# PS2_board.net
KiCad netlist of a schematic drawn in EAGLE
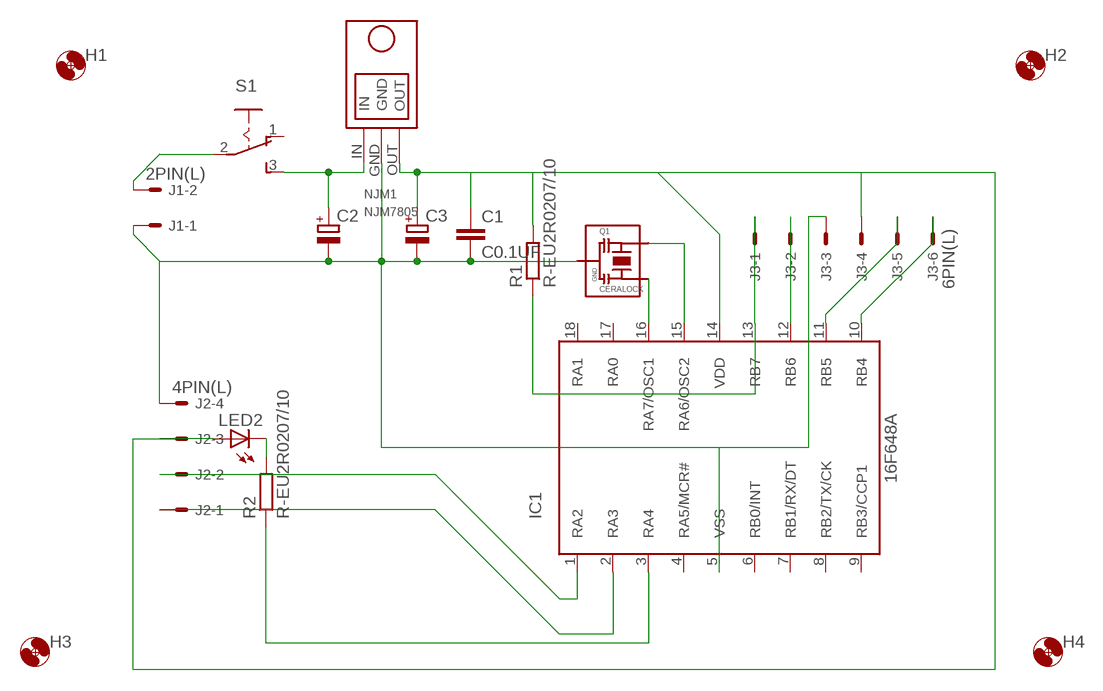
[diagram p0: schematic, sheet 1]

(export (version "E")
  (design (tool "Eeschema 10.0.6"))
  (components
    (comp (ref "C1")
      (value "C0.1UF")
      (footprint "eagle-import:C0.1UF")
      (libsource (lib "eagle-import") (part "C0.1UF"))
    )
    (comp (ref "C2")
      (value "CPOL-EU2-5MM")
      (footprint "eagle-import:E2-5")
      (libsource (lib "eagle-import") (part "CPOL-EU2-5MM"))
    )
    (comp (ref "C3")
      (value "CPOL-EU2-5MM")
      (footprint "eagle-import:E2-5")
      (libsource (lib "eagle-import") (part "CPOL-EU2-5MM"))
    )
    (comp (ref "H1")
      (value "HOLE3.3M3BOLT")
      (footprint "eagle-import:HOLE3.3")
      (libsource (lib "eagle-import") (part "HOLE3.3M3BOLT"))
    )
    (comp (ref "H2")
      (value "HOLE3.3M3BOLT")
      (footprint "eagle-import:HOLE3.3")
      (libsource (lib "eagle-import") (part "HOLE3.3M3BOLT"))
    )
    (comp (ref "H3")
      (value "HOLE3.3M3BOLT")
      (footprint "eagle-import:HOLE3.3")
      (libsource (lib "eagle-import") (part "HOLE3.3M3BOLT"))
    )
    (comp (ref "H4")
      (value "HOLE3.3M3BOLT")
      (footprint "eagle-import:HOLE3.3")
      (libsource (lib "eagle-import") (part "HOLE3.3M3BOLT"))
    )
    (comp (ref "IC1")
      (value "16F648A")
      (footprint "eagle-import:18PIN")
      (libsource (lib "eagle-import") (part "16F648A"))
    )
    (comp (ref "J1")
      (value "2PIN(L)")
      (footprint "eagle-import:2PL")
      (libsource (lib "eagle-import") (part "2PIN(L)"))
    )
    (comp (ref "J2")
      (value "4PIN(L)")
      (footprint "eagle-import:4PL")
      (libsource (lib "eagle-import") (part "4PIN(L)"))
    )
    (comp (ref "J3")
      (value "6PIN(L)")
      (footprint "eagle-import:6PL")
      (libsource (lib "eagle-import") (part "6PIN(L)"))
    )
    (comp (ref "LED2")
      (value "LED5MM")
      (footprint "eagle-import:LED5MM")
      (libsource (lib "eagle-import") (part "LED5MM"))
    )
    (comp (ref "NJM1")
      (value "NJM7805")
      (footprint "eagle-import:NJM7805")
      (libsource (lib "eagle-import") (part "NJM7805"))
    )
    (comp (ref "Q1")
      (value "CERALOCK")
      (footprint "eagle-import:CERALOCK")
      (libsource (lib "eagle-import") (part "CERALOCK"))
    )
    (comp (ref "R1")
      (value "R-EU2R0207/10")
      (footprint "eagle-import:0207_10")
      (libsource (lib "eagle-import") (part "R-EU2R0207/10"))
    )
    (comp (ref "R2")
      (value "R-EU2R0207/10")
      (footprint "eagle-import:0207_10")
      (libsource (lib "eagle-import") (part "R-EU2R0207/10"))
    )
    (comp (ref "S1")
      (value "SLIDESW")
      (footprint "eagle-import:SLIDESW")
      (libsource (lib "eagle-import") (part "SLIDESW"))
    )
  )
  (nets
    (net (code "1") (name "Net-(C2-Pad+)") (class "Default")
      (node (ref "C2") (pin "+") (pinfunction "+_+") (pintype "passive"))
      (node (ref "NJM1") (pin "IN") (pinfunction "IN_IN") (pintype "bidirectional"))
      (node (ref "S1") (pin "3") (pinfunction "3_3") (pintype "passive"))
    )
    (net (code "2") (name "Net-(IC1-RA2)") (class "Default")
      (node (ref "IC1") (pin "1") (pinfunction "RA2_1") (pintype "bidirectional"))
      (node (ref "J2") (pin "2") (pinfunction "S_2") (pintype "passive"))
    )
    (net (code "3") (name "Net-(IC1-RA3)") (class "Default")
      (node (ref "IC1") (pin "2") (pinfunction "RA3_2") (pintype "bidirectional"))
      (node (ref "J2") (pin "1") (pinfunction "S_1") (pintype "passive"))
    )
    (net (code "4") (name "Net-(IC1-RA4)") (class "Default")
      (node (ref "IC1") (pin "3") (pinfunction "RA4_3") (pintype "bidirectional"))
      (node (ref "R2") (pin "1") (pinfunction "1_1") (pintype "passive"))
    )
    (net (code "5") (name "Net-(IC1-RA6{slash}OSC2)") (class "Default")
      (node (ref "IC1") (pin "15") (pinfunction "RA6/OSC2_15") (pintype "bidirectional"))
      (node (ref "Q1") (pin "P$1") (pinfunction "P$1_P$1") (pintype "passive"))
    )
    (net (code "6") (name "Net-(IC1-RA7{slash}OSC1)") (class "Default")
      (node (ref "IC1") (pin "16") (pinfunction "RA7/OSC1_16") (pintype "bidirectional"))
      (node (ref "Q1") (pin "P$3") (pinfunction "P$3_P$3") (pintype "passive"))
    )
    (net (code "7") (name "Net-(IC1-RB4)") (class "Default")
      (node (ref "IC1") (pin "10") (pinfunction "RB4_10") (pintype "bidirectional"))
      (node (ref "J3") (pin "6") (pinfunction "S_6") (pintype "passive"))
    )
    (net (code "8") (name "Net-(IC1-RB5)") (class "Default")
      (node (ref "IC1") (pin "11") (pinfunction "RB5_11") (pintype "bidirectional"))
      (node (ref "J3") (pin "5") (pinfunction "S_5") (pintype "passive"))
    )
    (net (code "9") (name "Net-(IC1-RB6)") (class "Default")
      (node (ref "IC1") (pin "12") (pinfunction "RB6_12") (pintype "bidirectional"))
      (node (ref "J3") (pin "2") (pinfunction "S_2") (pintype "passive"))
    )
    (net (code "10") (name "Net-(IC1-RB7)") (class "Default")
      (node (ref "IC1") (pin "13") (pinfunction "RB7_13") (pintype "bidirectional"))
      (node (ref "J3") (pin "1") (pinfunction "S_1") (pintype "passive"))
      (node (ref "R1") (pin "1") (pinfunction "1_1") (pintype "passive"))
    )
    (net (code "11") (name "Net-(IC1-VDD)") (class "Default")
      (node (ref "C1") (pin "1") (pinfunction "1_1") (pintype "passive"))
      (node (ref "C3") (pin "+") (pinfunction "+_+") (pintype "passive"))
      (node (ref "IC1") (pin "14") (pinfunction "VDD_14") (pintype "power_in"))
      (node (ref "J2") (pin "3") (pinfunction "S_3") (pintype "passive"))
      (node (ref "J3") (pin "4") (pinfunction "S_4") (pintype "passive"))
      (node (ref "LED2") (pin "A") (pinfunction "A_A") (pintype "passive"))
      (node (ref "NJM1") (pin "OUT") (pinfunction "OUT_OUT") (pintype "bidirectional"))
      (node (ref "R1") (pin "2") (pinfunction "2_2") (pintype "passive"))
    )
    (net (code "12") (name "Net-(IC1-VSS)") (class "Default")
      (node (ref "C1") (pin "2") (pinfunction "2_2") (pintype "passive"))
      (node (ref "C2") (pin "-") (pinfunction "-_-") (pintype "passive"))
      (node (ref "C3") (pin "-") (pinfunction "-_-") (pintype "passive"))
      (node (ref "IC1") (pin "5") (pinfunction "VSS_5") (pintype "power_in"))
      (node (ref "J1") (pin "1") (pinfunction "S_1") (pintype "passive"))
      (node (ref "J2") (pin "4") (pinfunction "S_4") (pintype "passive"))
      (node (ref "J3") (pin "3") (pinfunction "S_3") (pintype "passive"))
      (node (ref "NJM1") (pin "GND") (pinfunction "GND_GND") (pintype "bidirectional"))
      (node (ref "Q1") (pin "P$2") (pinfunction "P$2_P$2") (pintype "passive"))
    )
    (net (code "13") (name "Net-(J1B-S)") (class "Default")
      (node (ref "J1") (pin "2") (pinfunction "S_2") (pintype "passive"))
      (node (ref "S1") (pin "2") (pinfunction "2_2") (pintype "passive"))
    )
    (net (code "14") (name "Net-(LED2-C)") (class "Default")
      (node (ref "LED2") (pin "K") (pinfunction "C_K") (pintype "passive"))
      (node (ref "R2") (pin "2") (pinfunction "2_2") (pintype "passive"))
    )
    (net (code "15") (name "unconnected-(IC1-RA0-Pad17)") (class "Default")
      (node (ref "IC1") (pin "17") (pinfunction "RA0_17") (pintype "bidirectional"))
    )
    (net (code "16") (name "unconnected-(IC1-RA1-Pad18)") (class "Default")
      (node (ref "IC1") (pin "18") (pinfunction "RA1_18") (pintype "bidirectional"))
    )
    (net (code "17") (name "unconnected-(IC1-RA5{slash}MCR#-Pad4)") (class "Default")
      (node (ref "IC1") (pin "4") (pinfunction "RA5/MCR#_4") (pintype "input"))
    )
    (net (code "18") (name "unconnected-(IC1-RB0{slash}INT-Pad6)") (class "Default")
      (node (ref "IC1") (pin "6") (pinfunction "RB0/INT_6") (pintype "bidirectional"))
    )
    (net (code "19") (name "unconnected-(IC1-RB1{slash}RX{slash}DT-Pad7)") (class "Default")
      (node (ref "IC1") (pin "7") (pinfunction "RB1/RX/DT_7") (pintype "bidirectional"))
    )
    (net (code "20") (name "unconnected-(IC1-RB2{slash}TX{slash}CK-Pad8)") (class "Default")
      (node (ref "IC1") (pin "8") (pinfunction "RB2/TX/CK_8") (pintype "bidirectional"))
    )
    (net (code "21") (name "unconnected-(IC1-RB3{slash}CCP1-Pad9)") (class "Default")
      (node (ref "IC1") (pin "9") (pinfunction "RB3/CCP1_9") (pintype "bidirectional"))
    )
    (net (code "22") (name "unconnected-(S1-Pad1)") (class "Default")
      (node (ref "S1") (pin "1") (pinfunction "1_1") (pintype "passive"))
    )
  )
)
